# schematic_ad15.net
KiCad netlist of a schematic drawn in Altium Designer
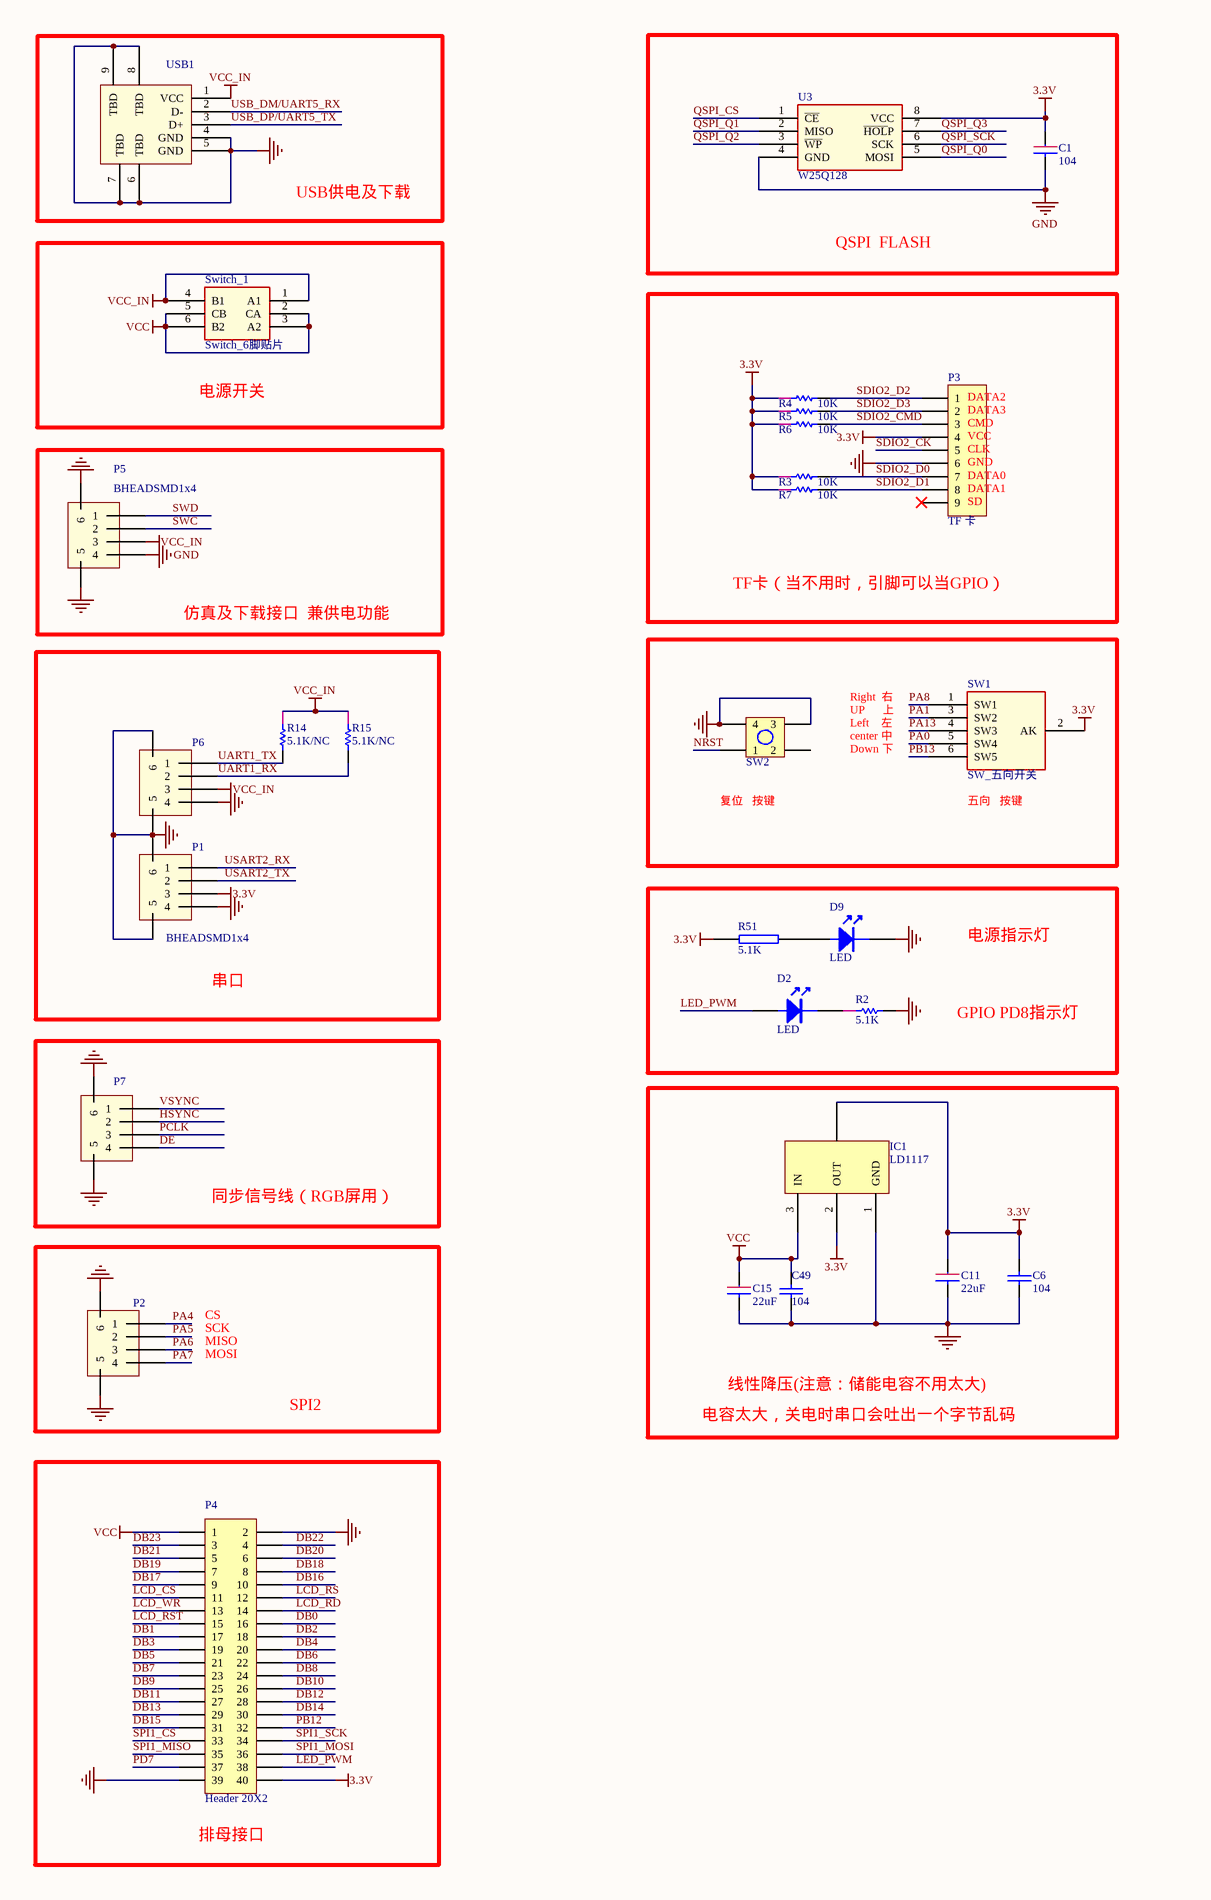
[diagram p0: schematic_ad15.SchDoc, left]
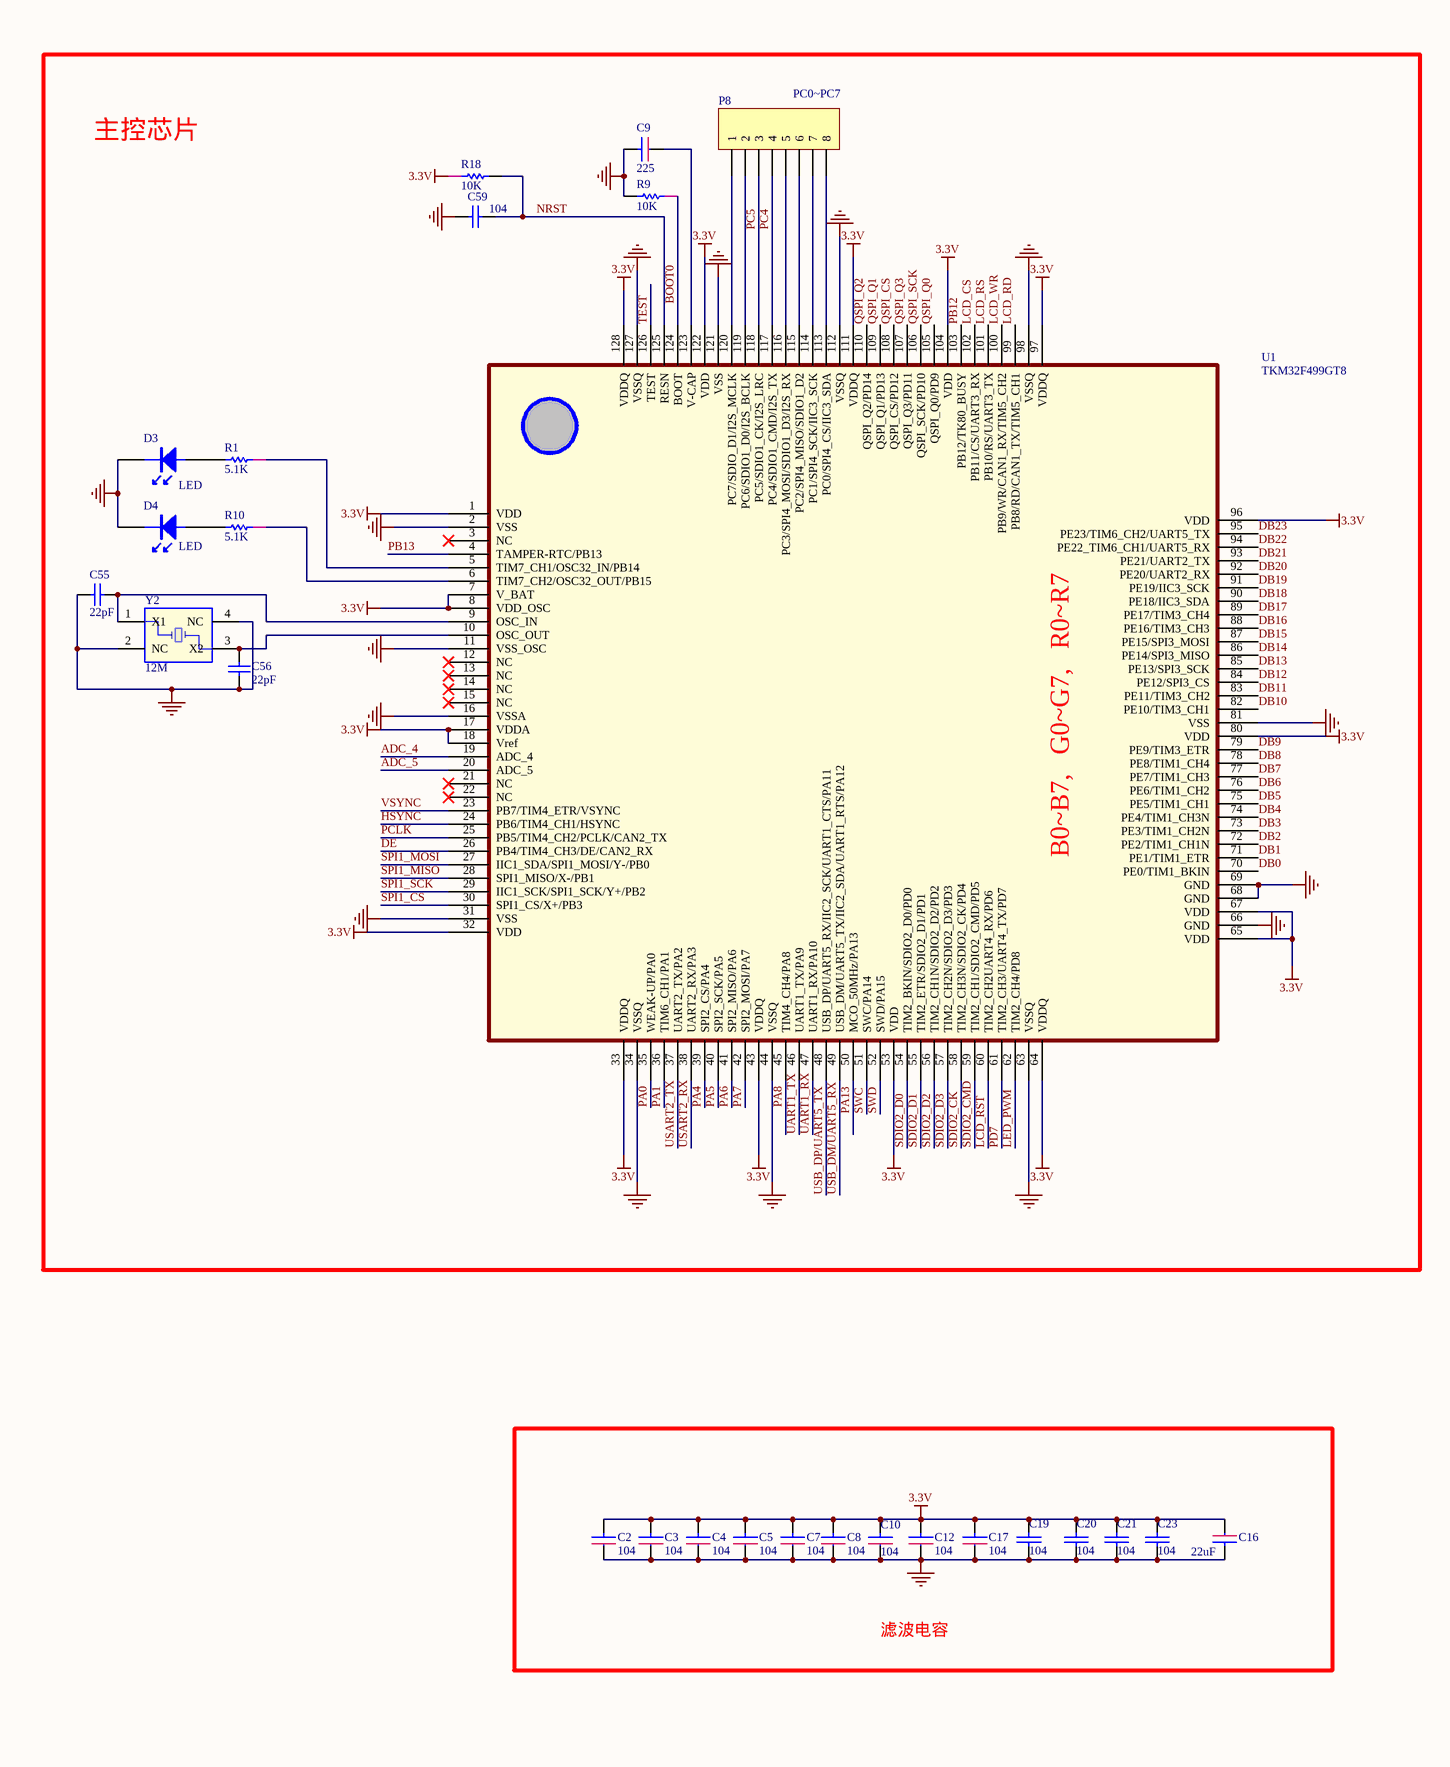
[diagram p1: schematic_ad15.SchDoc, right]

(export (version "E")
  (design (tool "Eeschema 10.0.6"))
  (components
    (comp (ref "C1") (value "104") (footprint "C0402-1") (libsource (lib "Tiky") (part "cap")))
    (comp (ref "C2") (value "104") (footprint "C0402-1") (libsource (lib "Tiky") (part "cap")))
    (comp (ref "C3") (value "104") (footprint "C0402-1") (libsource (lib "Tiky") (part "cap")))
    (comp (ref "C4") (value "104") (footprint "C0402-1") (libsource (lib "Tiky") (part "cap")))
    (comp (ref "C5") (value "104") (footprint "C0402-1") (libsource (lib "Tiky") (part "cap")))
    (comp (ref "C6")
      (value "104")
      (footprint "C0402-1")
      (description "Capacitor")
      (libsource (lib "Miscellaneous Devices") (part "CAP"))
    )
    (comp (ref "C7") (value "104") (footprint "C0402-1") (libsource (lib "Tiky") (part "cap")))
    (comp (ref "C8") (value "104") (footprint "C0402-1") (libsource (lib "Tiky") (part "cap")))
    (comp (ref "C9") (value "225") (footprint "C0603-2") (libsource (lib "Tiky") (part "cap")))
    (comp (ref "C10") (value "104") (footprint "C0402-1") (libsource (lib "Tiky") (part "cap")))
    (comp (ref "C11") (value "22uF") (footprint "Case B 3528") (libsource (lib "Tiky") (part "cap")))
    (comp (ref "C12") (value "104") (footprint "C0402-1") (libsource (lib "Tiky") (part "cap")))
    (comp (ref "C15") (value "22uF") (footprint "Case B 3528") (libsource (lib "Tiky") (part "cap")))
    (comp (ref "C16") (value "22uF") (footprint "C0805-3") (libsource (lib "Tiky") (part "cap")))
    (comp (ref "C17") (value "104") (footprint "C0402-1") (libsource (lib "Tiky") (part "cap")))
    (comp (ref "C19")
      (value "104")
      (footprint "C0402-1")
      (description "Capacitor")
      (libsource (lib "*") (part "CAP"))
    )
    (comp (ref "C20")
      (value "104")
      (footprint "C0402-1")
      (description "Capacitor")
      (libsource (lib "*") (part "CAP"))
    )
    (comp (ref "C21")
      (value "104")
      (footprint "C0402-1")
      (description "Capacitor")
      (libsource (lib "*") (part "CAP"))
    )
    (comp (ref "C23")
      (value "104")
      (footprint "C0402-1")
      (description "Capacitor")
      (libsource (lib "*") (part "CAP"))
    )
    (comp (ref "C49")
      (value "104")
      (footprint "C0402-1")
      (description "Capacitor")
      (libsource (lib "*") (part "CAP"))
    )
    (comp (ref "C55")
      (value "22pF")
      (footprint "C0402-2")
      (description "Capacitor")
      (fields (field (name "PUBLISHER") "Altium Limited"))
      (libsource (lib "Miscellaneous Devices") (part "Cap"))
    )
    (comp (ref "C56")
      (value "22pF")
      (footprint "C0402-2")
      (description "Capacitor")
      (fields (field (name "PUBLISHER") "Altium Limited"))
      (libsource (lib "Miscellaneous Devices") (part "Cap"))
    )
    (comp (ref "C59")
      (value "104")
      (footprint "C0402-1")
      (description "Capacitor")
      (fields (field (name "PUBLISHER") "Altium Limited"))
      (libsource (lib "") (part "CAP_1"))
    )
    (comp (ref "D2") (value "LED") (footprint "D0603") (libsource (lib "*") (part "LED")))
    (comp (ref "D3") (value "LED") (footprint "D0603") (libsource (lib "*") (part "LED")))
    (comp (ref "D4") (value "LED") (footprint "D0603") (libsource (lib "*") (part "LED")))
    (comp (ref "D9") (value "LED") (footprint "D0603") (libsource (lib "*") (part "LED")))
    (comp (ref "IC1") (value "LD1117") (footprint "SOT223") (libsource (lib "Tiky") (part "LD1117")))
    (comp (ref "P1")
      (value "BHEADSMD1x4")
      (footprint "BHEADSMD1x4")
      (libsource (lib "Tiky") (part "BHEADSMD1x4"))
    )
    (comp (ref "P2")
      (value "BHEADSMD1x4")
      (footprint "BHEADSMD1x4")
      (libsource (lib "Tiky") (part "BHEADSMD1x4"))
    )
    (comp (ref "P3")
      (value "TF 卡")
      (footprint "Micro_SD")
      (description "Header, 9-Pin")
      (fields (field (name "PUBLISHER") "Altium Limited"))
      (libsource (lib "Miscellaneous Connectors") (part "Header 9"))
    )
    (comp (ref "P4")
      (value "Header 20X2")
      (footprint "P_Head_2x20")
      (description "Header, 20-Pin, Dual row")
      (fields (field (name "PUBLISHER") "Altium Limited"))
      (libsource (lib "Miscellaneous Connectors") (part "Header 20X2"))
    )
    (comp (ref "P5")
      (value "BHEADSMD1x4")
      (footprint "BHEADSMD1x4")
      (libsource (lib "Tiky") (part "BHEADSMD1x4"))
    )
    (comp (ref "P6")
      (value "BHEADSMD1x4")
      (footprint "BHEADSMD1x4")
      (libsource (lib "Tiky") (part "BHEADSMD1x4"))
    )
    (comp (ref "P7")
      (value "BHEADSMD1x4")
      (footprint "BHEADSMD1x4")
      (libsource (lib "Tiky") (part "BHEADSMD1x4"))
    )
    (comp (ref "P8")
      (value "PC0~PC7")
      (footprint "HDR1X8")
      (description "Header, 8-Pin")
      (fields (field (name "PUBLISHER") "Altium Limited"))
      (libsource (lib "Miscellaneous Connectors") (part "Header 8"))
    )
    (comp (ref "R1") (value "5.1K") (footprint "R0402") (libsource (lib "Tiky") (part "Resistor")))
    (comp (ref "R2") (value "5.1K") (footprint "R0402") (libsource (lib "Tiky") (part "Resistor")))
    (comp (ref "R3") (value "10K") (footprint "R0402") (libsource (lib "Tiky") (part "Resistor")))
    (comp (ref "R4") (value "10K") (footprint "R0402") (libsource (lib "Tiky") (part "Resistor")))
    (comp (ref "R5") (value "10K") (footprint "R0402") (libsource (lib "Tiky") (part "Resistor")))
    (comp (ref "R6") (value "10K") (footprint "R0402") (libsource (lib "Tiky") (part "Resistor")))
    (comp (ref "R7") (value "10K") (footprint "R0402") (libsource (lib "Tiky") (part "Resistor")))
    (comp (ref "R9") (value "10K") (footprint "R0402") (libsource (lib "Tiky") (part "Resistor")))
    (comp (ref "R10") (value "5.1K") (footprint "R0402") (libsource (lib "Tiky") (part "Resistor")))
    (comp (ref "R14") (value "5.1K/NC") (footprint "R0402") (libsource (lib "Tiky") (part "Resistor")))
    (comp (ref "R15") (value "5.1K/NC") (footprint "R0402") (libsource (lib "Tiky") (part "Resistor")))
    (comp (ref "R18") (value "10K") (footprint "R0402") (libsource (lib "Tiky") (part "Resistor")))
    (comp (ref "R51") (value "5.1K") (footprint "R0402") (libsource (lib "*") (part "RES2")))
    (comp (ref "SW1") (value "SW_五向开关") (footprint "五向开关") (libsource (lib "Tiky") (part "SW_五向开关")))
    (comp (ref "SW2") (value "SW") (footprint "SW") (libsource (lib "Tiky") (part "SW")))
    (comp (ref "Switch_1")
      (value "Switch_6脚贴片")
      (footprint "Switch_6脚贴片")
      (libsource (lib "Tiky") (part "Switch_6脚贴片"))
    )
    (comp (ref "U1")
      (value "TKM32F499GT8")
      (footprint "LQFP128")
      (libsource (lib "Tiky") (part "TKM32F499GT8"))
    )
    (comp (ref "U3") (value "W25Q128") (footprint "SOP8-215-50") (libsource (lib "Tiky") (part "W25Q16")))
    (comp (ref "USB1")
      (value "Micro USB")
      (footprint "MicroUSB_带定位柱")
      (libsource (lib "Tiky") (part "Mini USB"))
    )
    (comp (ref "Y2") (value "12M") (footprint "X3225") (libsource (lib "Tiky") (part "晶振_无源_4PIN_SMD")))
  )
  (nets
    (net (code "1") (name "/ADC_4") (class "Default")
      (node (ref "U1") (pin "19") (pinfunction "ADC_4_19") (pintype "passive"))
    )
    (net (code "2") (name "/ADC_5") (class "Default")
      (node (ref "U1") (pin "20") (pinfunction "ADC_5_20") (pintype "passive"))
    )
    (net (code "3") (name "/BOOT0") (class "Default")
      (node (ref "R9") (pin "1") (pinfunction "1_1") (pintype "passive"))
      (node (ref "U1") (pin "124") (pinfunction "BOOT_124") (pintype "passive"))
    )
    (net (code "4") (name "/DB0") (class "Default")
      (node (ref "P4") (pin "16") (pinfunction "16_16") (pintype "passive"))
      (node (ref "U1") (pin "70") (pinfunction "PE0/TIM1_BKIN_70") (pintype "passive"))
    )
    (net (code "5") (name "/DB1") (class "Default")
      (node (ref "P4") (pin "17") (pinfunction "17_17") (pintype "passive"))
      (node (ref "U1") (pin "71") (pinfunction "PE1/TIM1_ETR_71") (pintype "passive"))
    )
    (net (code "6") (name "/DB2") (class "Default")
      (node (ref "P4") (pin "18") (pinfunction "18_18") (pintype "passive"))
      (node (ref "U1") (pin "72") (pinfunction "PE2/TIM1_CH1N_72") (pintype "passive"))
    )
    (net (code "7") (name "/DB3") (class "Default")
      (node (ref "P4") (pin "19") (pinfunction "19_19") (pintype "passive"))
      (node (ref "U1") (pin "73") (pinfunction "PE3/TIM1_CH2N_73") (pintype "passive"))
    )
    (net (code "8") (name "/DB4") (class "Default")
      (node (ref "P4") (pin "20") (pinfunction "20_20") (pintype "passive"))
      (node (ref "U1") (pin "74") (pinfunction "PE4/TIM1_CH3N_74") (pintype "passive"))
    )
    (net (code "9") (name "/DB5") (class "Default")
      (node (ref "P4") (pin "21") (pinfunction "21_21") (pintype "passive"))
      (node (ref "U1") (pin "75") (pinfunction "PE5/TIM1_CH1_75") (pintype "passive"))
    )
    (net (code "10") (name "/DB6") (class "Default")
      (node (ref "P4") (pin "22") (pinfunction "22_22") (pintype "passive"))
      (node (ref "U1") (pin "76") (pinfunction "PE6/TIM1_CH2_76") (pintype "passive"))
    )
    (net (code "11") (name "/DB7") (class "Default")
      (node (ref "P4") (pin "23") (pinfunction "23_23") (pintype "passive"))
      (node (ref "U1") (pin "77") (pinfunction "PE7/TIM1_CH3_77") (pintype "passive"))
    )
    (net (code "12") (name "/DB8") (class "Default")
      (node (ref "P4") (pin "24") (pinfunction "24_24") (pintype "passive"))
      (node (ref "U1") (pin "78") (pinfunction "PE8/TIM1_CH4_78") (pintype "passive"))
    )
    (net (code "13") (name "/DB9") (class "Default")
      (node (ref "P4") (pin "25") (pinfunction "25_25") (pintype "passive"))
      (node (ref "U1") (pin "79") (pinfunction "PE9/TIM3_ETR_79") (pintype "passive"))
    )
    (net (code "14") (name "/DB10") (class "Default")
      (node (ref "P4") (pin "26") (pinfunction "26_26") (pintype "passive"))
      (node (ref "U1") (pin "82") (pinfunction "PE10/TIM3_CH1_82") (pintype "passive"))
    )
    (net (code "15") (name "/DB11") (class "Default")
      (node (ref "P4") (pin "27") (pinfunction "27_27") (pintype "passive"))
      (node (ref "U1") (pin "83") (pinfunction "PE11/TIM3_CH2_83") (pintype "passive"))
    )
    (net (code "16") (name "/DB12") (class "Default")
      (node (ref "P4") (pin "28") (pinfunction "28_28") (pintype "passive"))
      (node (ref "U1") (pin "84") (pinfunction "PE12/SPI3_CS_84") (pintype "passive"))
    )
    (net (code "17") (name "/DB13") (class "Default")
      (node (ref "P4") (pin "29") (pinfunction "29_29") (pintype "passive"))
      (node (ref "U1") (pin "85") (pinfunction "PE13/SPI3_SCK_85") (pintype "passive"))
    )
    (net (code "18") (name "/DB14") (class "Default")
      (node (ref "P4") (pin "30") (pinfunction "30_30") (pintype "passive"))
      (node (ref "U1") (pin "86") (pinfunction "PE14/SPI3_MISO_86") (pintype "passive"))
    )
    (net (code "19") (name "/DB15") (class "Default")
      (node (ref "P4") (pin "31") (pinfunction "31_31") (pintype "passive"))
      (node (ref "U1") (pin "87") (pinfunction "PE15/SPI3_MOSI_87") (pintype "passive"))
    )
    (net (code "20") (name "/DB16") (class "Default")
      (node (ref "P4") (pin "10") (pinfunction "10_10") (pintype "passive"))
      (node (ref "U1") (pin "88") (pinfunction "PE16/TIM3_CH3_88") (pintype "passive"))
    )
    (net (code "21") (name "/DB17") (class "Default")
      (node (ref "P4") (pin "9") (pinfunction "9_9") (pintype "passive"))
      (node (ref "U1") (pin "89") (pinfunction "PE17/TIM3_CH4_89") (pintype "passive"))
    )
    (net (code "22") (name "/DB18") (class "Default")
      (node (ref "P4") (pin "8") (pinfunction "8_8") (pintype "passive"))
      (node (ref "U1") (pin "90") (pinfunction "PE18/IIC3_SDA_90") (pintype "passive"))
    )
    (net (code "23") (name "/DB19") (class "Default")
      (node (ref "P4") (pin "7") (pinfunction "7_7") (pintype "passive"))
      (node (ref "U1") (pin "91") (pinfunction "PE19/IIC3_SCK_91") (pintype "passive"))
    )
    (net (code "24") (name "/DB20") (class "Default")
      (node (ref "P4") (pin "6") (pinfunction "6_6") (pintype "passive"))
      (node (ref "U1") (pin "92") (pinfunction "PE20/UART2_RX_92") (pintype "passive"))
    )
    (net (code "25") (name "/DB21") (class "Default")
      (node (ref "P4") (pin "5") (pinfunction "5_5") (pintype "passive"))
      (node (ref "U1") (pin "93") (pinfunction "PE21/UART2_TX_93") (pintype "passive"))
    )
    (net (code "26") (name "/DB22") (class "Default")
      (node (ref "P4") (pin "4") (pinfunction "4_4") (pintype "passive"))
      (node (ref "U1") (pin "94") (pinfunction "PE22_TIM6_CH1/UART5_RX_94") (pintype "passive"))
    )
    (net (code "27") (name "/DB23") (class "Default")
      (node (ref "P4") (pin "3") (pinfunction "3_3") (pintype "passive"))
      (node (ref "U1") (pin "95") (pinfunction "PE23/TIM6_CH2/UART5_TX_95") (pintype "passive"))
    )
    (net (code "28") (name "/DE") (class "Default")
      (node (ref "P7") (pin "4") (pinfunction "4_4") (pintype "passive"))
      (node (ref "U1") (pin "26") (pinfunction "PB4/TIM4_CH3/DE/CAN2_RX_26") (pintype "passive"))
    )
    (net (code "29") (name "/HSYNC") (class "Default")
      (node (ref "P7") (pin "2") (pinfunction "2_2") (pintype "passive"))
      (node (ref "U1") (pin "24") (pinfunction "PB6/TIM4_CH1/HSYNC_24") (pintype "passive"))
    )
    (net (code "30") (name "/LCD_CS") (class "Default")
      (node (ref "P4") (pin "11") (pinfunction "11_11") (pintype "passive"))
      (node (ref "U1") (pin "102") (pinfunction "PB11/CS/UART3_RX_102") (pintype "passive"))
    )
    (net (code "31") (name "/LCD_RD") (class "Default")
      (node (ref "P4") (pin "14") (pinfunction "14_14") (pintype "passive"))
      (node (ref "U1") (pin "99") (pinfunction "PB8/RD/CAN1_TX/TIM5_CH1_99") (pintype "passive"))
    )
    (net (code "32") (name "/LCD_RS") (class "Default")
      (node (ref "P4") (pin "12") (pinfunction "12_12") (pintype "passive"))
      (node (ref "U1") (pin "101") (pinfunction "PB10/RS/UART3_TX_101") (pintype "passive"))
    )
    (net (code "33") (name "/LCD_RST") (class "Default")
      (node (ref "P4") (pin "15") (pinfunction "15_15") (pintype "passive"))
      (node (ref "U1") (pin "60") (pinfunction "TIM2_CH2UART4_RX/PD6_60") (pintype "passive"))
    )
    (net (code "34") (name "/LCD_WR") (class "Default")
      (node (ref "P4") (pin "13") (pinfunction "13_13") (pintype "passive"))
      (node (ref "U1") (pin "100") (pinfunction "PB9/WR/CAN1_RX/TIM5_CH2_100") (pintype "passive"))
    )
    (net (code "35") (name "/LED_PWM") (class "Default")
      (node (ref "D2") (pin "1") (pinfunction "1_1") (pintype "passive"))
      (node (ref "P4") (pin "38") (pinfunction "38_38") (pintype "passive"))
      (node (ref "U1") (pin "62") (pinfunction "TIM2_CH4/PD8_62") (pintype "passive"))
    )
    (net (code "36") (name "/NRST") (class "Default")
      (node (ref "C59") (pin "2") (pinfunction "2_2") (pintype "passive"))
      (node (ref "R18") (pin "2") (pinfunction "2_2") (pintype "passive"))
      (node (ref "SW2") (pin "1") (pinfunction "1_1") (pintype "passive"))
      (node (ref "U1") (pin "125") (pinfunction "RESN_125") (pintype "passive"))
    )
    (net (code "37") (name "/PA0") (class "Default")
      (node (ref "SW1") (pin "5") (pinfunction "SW4_5") (pintype "passive"))
      (node (ref "U1") (pin "35") (pinfunction "WEAK-UP/PA0_35") (pintype "passive"))
    )
    (net (code "38") (name "/PA1") (class "Default")
      (node (ref "SW1") (pin "3") (pinfunction "SW2_3") (pintype "passive"))
      (node (ref "U1") (pin "36") (pinfunction "TIM6_CH1/PA1_36") (pintype "passive"))
    )
    (net (code "39") (name "/PA4") (class "Default")
      (node (ref "P2") (pin "1") (pinfunction "1_1") (pintype "passive"))
      (node (ref "U1") (pin "39") (pinfunction "SPI2_CS/PA4_39") (pintype "passive"))
    )
    (net (code "40") (name "/PA5") (class "Default")
      (node (ref "P2") (pin "2") (pinfunction "2_2") (pintype "passive"))
      (node (ref "U1") (pin "40") (pinfunction "SPI2_SCK/PA5_40") (pintype "passive"))
    )
    (net (code "41") (name "/PA6") (class "Default")
      (node (ref "P2") (pin "3") (pinfunction "3_3") (pintype "passive"))
      (node (ref "U1") (pin "41") (pinfunction "SPI2_MISO/PA6_41") (pintype "passive"))
    )
    (net (code "42") (name "/PA7") (class "Default")
      (node (ref "P2") (pin "4") (pinfunction "4_4") (pintype "passive"))
      (node (ref "U1") (pin "42") (pinfunction "SPI2_MOSI/PA7_42") (pintype "passive"))
    )
    (net (code "43") (name "/PA8") (class "Default")
      (node (ref "SW1") (pin "1") (pinfunction "SW1_1") (pintype "passive"))
      (node (ref "U1") (pin "45") (pinfunction "TIM4_CH4/PA8_45") (pintype "passive"))
    )
    (net (code "44") (name "/PA13") (class "Default")
      (node (ref "SW1") (pin "4") (pinfunction "SW3_4") (pintype "passive"))
      (node (ref "U1") (pin "50") (pinfunction "MCO_50MHz/PA13_50") (pintype "passive"))
    )
    (net (code "45") (name "/PB12") (class "Default")
      (node (ref "P4") (pin "32") (pinfunction "32_32") (pintype "passive"))
      (node (ref "U1") (pin "103") (pinfunction "PB12/TK80_BUSY_103") (pintype "passive"))
    )
    (net (code "46") (name "/PB13") (class "Default")
      (node (ref "SW1") (pin "6") (pinfunction "SW5_6") (pintype "passive"))
      (node (ref "U1") (pin "4") (pinfunction "TAMPER-RTC/PB13_4") (pintype "passive"))
    )
    (net (code "47") (name "/PC4") (class "Default")
      (node (ref "P8") (pin "4") (pinfunction "4_4") (pintype "passive"))
      (node (ref "U1") (pin "117") (pinfunction "PC4/SDIO1_CMD/I2S_TX_117") (pintype "passive"))
    )
    (net (code "48") (name "/PC5") (class "Default")
      (node (ref "P8") (pin "3") (pinfunction "3_3") (pintype "passive"))
      (node (ref "U1") (pin "118") (pinfunction "PC5/SDIO1_CK/I2S_LRC_118") (pintype "passive"))
    )
    (net (code "49") (name "/PCLK") (class "Default")
      (node (ref "P7") (pin "3") (pinfunction "3_3") (pintype "passive"))
      (node (ref "U1") (pin "25") (pinfunction "PB5/TIM4_CH2/PCLK/CAN2_TX_25") (pintype "passive"))
    )
    (net (code "50") (name "/PD7") (class "Default")
      (node (ref "P4") (pin "37") (pinfunction "37_37") (pintype "passive"))
      (node (ref "U1") (pin "61") (pinfunction "TIM2_CH3/UART4_TX/PD7_61") (pintype "passive"))
    )
    (net (code "51") (name "/QSPI_CS") (class "Default")
      (node (ref "U1") (pin "108") (pinfunction "QSPI_CS/PD12_108") (pintype "passive"))
      (node (ref "U3") (pin "1") (pinfunction "~{CE}_1") (pintype "passive"))
    )
    (net (code "52") (name "/QSPI_Q0") (class "Default")
      (node (ref "U1") (pin "105") (pinfunction "QSPI_Q0/PD9_105") (pintype "passive"))
      (node (ref "U3") (pin "5") (pinfunction "MOSI_5") (pintype "passive"))
    )
    (net (code "53") (name "/QSPI_Q1") (class "Default")
      (node (ref "U1") (pin "109") (pinfunction "QSPI_Q1/PD13_109") (pintype "passive"))
      (node (ref "U3") (pin "2") (pinfunction "MISO_2") (pintype "passive"))
    )
    (net (code "54") (name "/QSPI_Q2") (class "Default")
      (node (ref "U1") (pin "110") (pinfunction "QSPI_Q2/PD14_110") (pintype "passive"))
      (node (ref "U3") (pin "3") (pinfunction "~{WP}_3") (pintype "passive"))
    )
    (net (code "55") (name "/QSPI_Q3") (class "Default")
      (node (ref "U1") (pin "107") (pinfunction "QSPI_Q3/PD11_107") (pintype "passive"))
      (node (ref "U3") (pin "7") (pinfunction "~{HOL}P_7") (pintype "passive"))
    )
    (net (code "56") (name "/QSPI_SCK") (class "Default")
      (node (ref "U1") (pin "106") (pinfunction "QSPI_SCK/PD10_106") (pintype "passive"))
      (node (ref "U3") (pin "6") (pinfunction "SCK_6") (pintype "passive"))
    )
    (net (code "57") (name "/SDIO2_CK") (class "Default")
      (node (ref "P3") (pin "5") (pinfunction "5_5") (pintype "passive"))
      (node (ref "U1") (pin "58") (pinfunction "TIM2_CH3N/SDIO2_CK/PD4_58") (pintype "passive"))
    )
    (net (code "58") (name "/SDIO2_CMD") (class "Default")
      (node (ref "P3") (pin "3") (pinfunction "3_3") (pintype "passive"))
      (node (ref "R6") (pin "2") (pinfunction "2_2") (pintype "passive"))
      (node (ref "U1") (pin "59") (pinfunction "TIM2_CH1/SDIO2_CMD/PD5_59") (pintype "passive"))
    )
    (net (code "59") (name "/SDIO2_D0") (class "Default")
      (node (ref "P3") (pin "7") (pinfunction "7_7") (pintype "passive"))
      (node (ref "R3") (pin "2") (pinfunction "2_2") (pintype "passive"))
      (node (ref "U1") (pin "54") (pinfunction "TIM2_BKIN/SDIO2_D0/PD0_54") (pintype "passive"))
    )
    (net (code "60") (name "/SDIO2_D1") (class "Default")
      (node (ref "P3") (pin "8") (pinfunction "8_8") (pintype "passive"))
      (node (ref "R7") (pin "2") (pinfunction "2_2") (pintype "passive"))
      (node (ref "U1") (pin "55") (pinfunction "TIM2_ETR/SDIO2_D1/PD1_55") (pintype "passive"))
    )
    (net (code "61") (name "/SDIO2_D2") (class "Default")
      (node (ref "P3") (pin "1") (pinfunction "1_1") (pintype "passive"))
      (node (ref "R4") (pin "2") (pinfunction "2_2") (pintype "passive"))
      (node (ref "U1") (pin "56") (pinfunction "TIM2_CH1N/SDIO2_D2/PD2_56") (pintype "passive"))
    )
    (net (code "62") (name "/SDIO2_D3") (class "Default")
      (node (ref "P3") (pin "2") (pinfunction "2_2") (pintype "passive"))
      (node (ref "R5") (pin "2") (pinfunction "2_2") (pintype "passive"))
      (node (ref "U1") (pin "57") (pinfunction "TIM2_CH2N/SDIO2_D3/PD3_57") (pintype "passive"))
    )
    (net (code "63") (name "/SPI1_CS") (class "Default")
      (node (ref "P4") (pin "33") (pinfunction "33_33") (pintype "passive"))
      (node (ref "U1") (pin "30") (pinfunction "SPI1_CS/X+/PB3_30") (pintype "passive"))
    )
    (net (code "64") (name "/SPI1_MISO") (class "Default")
      (node (ref "P4") (pin "35") (pinfunction "35_35") (pintype "passive"))
      (node (ref "U1") (pin "28") (pinfunction "SPI1_MISO/X-/PB1_28") (pintype "passive"))
    )
    (net (code "65") (name "/SPI1_MOSI") (class "Default")
      (node (ref "P4") (pin "36") (pinfunction "36_36") (pintype "passive"))
      (node (ref "U1") (pin "27") (pinfunction "IIC1_SDA/SPI1_MOSI/Y-/PB0_27") (pintype "passive"))
    )
    (net (code "66") (name "/SPI1_SCK") (class "Default")
      (node (ref "P4") (pin "34") (pinfunction "34_34") (pintype "passive"))
      (node (ref "U1") (pin "29") (pinfunction "IIC1_SCK/SPI1_SCK/Y+/PB2_29") (pintype "passive"))
    )
    (net (code "67") (name "/SWC") (class "Default")
      (node (ref "P5") (pin "2") (pinfunction "2_2") (pintype "passive"))
      (node (ref "U1") (pin "51") (pinfunction "SWC/PA14_51") (pintype "passive"))
    )
    (net (code "68") (name "/SWD") (class "Default")
      (node (ref "P5") (pin "1") (pinfunction "1_1") (pintype "passive"))
      (node (ref "U1") (pin "52") (pinfunction "SWD/PA15_52") (pintype "passive"))
    )
    (net (code "69") (name "/TEST") (class "Default")
      (node (ref "U1") (pin "126") (pinfunction "TEST_126") (pintype "passive"))
    )
    (net (code "70") (name "/UART1_RX") (class "Default")
      (node (ref "P6") (pin "2") (pinfunction "2_2") (pintype "passive"))
      (node (ref "R15") (pin "2") (pinfunction "2_2") (pintype "passive"))
      (node (ref "U1") (pin "47") (pinfunction "UART1_RX/PA10_47") (pintype "passive"))
    )
    (net (code "71") (name "/UART1_TX") (class "Default")
      (node (ref "P6") (pin "1") (pinfunction "1_1") (pintype "passive"))
      (node (ref "R14") (pin "2") (pinfunction "2_2") (pintype "passive"))
      (node (ref "U1") (pin "46") (pinfunction "UART1_TX/PA9_46") (pintype "passive"))
    )
    (net (code "72") (name "/USART2_RX") (class "Default")
      (node (ref "P1") (pin "1") (pinfunction "1_1") (pintype "passive"))
      (node (ref "U1") (pin "38") (pinfunction "UART2_RX/PA3_38") (pintype "passive"))
    )
    (net (code "73") (name "/USART2_TX") (class "Default")
      (node (ref "P1") (pin "2") (pinfunction "2_2") (pintype "passive"))
      (node (ref "U1") (pin "37") (pinfunction "UART2_TX/PA2_37") (pintype "passive"))
    )
    (net (code "74") (name "/USB_DM{slash}UART5_RX") (class "Default")
      (node (ref "U1") (pin "49") (pinfunction "USB_DM/UART5_TX/IIC2_SDA/UART1_RTS/PA12_49") (pintype "passive"))
      (node (ref "USB1") (pin "2") (pinfunction "D-_2") (pintype "passive"))
    )
    (net (code "75") (name "/USB_DP{slash}UART5_TX") (class "Default")
      (node (ref "U1") (pin "48") (pinfunction "USB_DP/UART5_RX/IIC2_SCK/UART1_CTS/PA11_48") (pintype "passive"))
      (node (ref "USB1") (pin "3") (pinfunction "D+_3") (pintype "passive"))
    )
    (net (code "76") (name "/VSYNC") (class "Default")
      (node (ref "P7") (pin "1") (pinfunction "1_1") (pintype "passive"))
      (node (ref "U1") (pin "23") (pinfunction "PB7/TIM4_ETR/VSYNC_23") (pintype "passive"))
    )
    (net (code "77") (name "3.3V") (class "Default")
      (node (ref "C1") (pin "1") (pinfunction "1_1") (pintype "passive"))
      (node (ref "C10") (pin "2") (pinfunction "2_2") (pintype "passive"))
      (node (ref "C11") (pin "1") (pinfunction "1_1") (pintype "passive"))
      (node (ref "C12") (pin "2") (pinfunction "2_2") (pintype "passive"))
      (node (ref "C16") (pin "1") (pinfunction "1_1") (pintype "passive"))
      (node (ref "C17") (pin "2") (pinfunction "2_2") (pintype "passive"))
      (node (ref "C19") (pin "2") (pinfunction "2_2") (pintype "passive"))
      (node (ref "C2") (pin "2") (pinfunction "2_2") (pintype "passive"))
      (node (ref "C20") (pin "2") (pinfunction "2_2") (pintype "passive"))
      (node (ref "C21") (pin "2") (pinfunction "2_2") (pintype "passive"))
      (node (ref "C23") (pin "2") (pinfunction "2_2") (pintype "passive"))
      (node (ref "C3") (pin "2") (pinfunction "2_2") (pintype "passive"))
      (node (ref "C4") (pin "2") (pinfunction "2_2") (pintype "passive"))
      (node (ref "C5") (pin "2") (pinfunction "2_2") (pintype "passive"))
      (node (ref "C6") (pin "1") (pinfunction "1_1") (pintype "passive"))
      (node (ref "C7") (pin "2") (pinfunction "2_2") (pintype "passive"))
      (node (ref "C8") (pin "2") (pinfunction "2_2") (pintype "passive"))
      (node (ref "IC1") (pin "2") (pinfunction "OUT_2") (pintype "passive"))
      (node (ref "P1") (pin "3") (pinfunction "3_3") (pintype "passive"))
      (node (ref "P3") (pin "4") (pinfunction "4_4") (pintype "passive"))
      (node (ref "P4") (pin "40") (pinfunction "40_40") (pintype "passive"))
      (node (ref "R18") (pin "1") (pinfunction "1_1") (pintype "passive"))
      (node (ref "R3") (pin "1") (pinfunction "1_1") (pintype "passive"))
      (node (ref "R4") (pin "1") (pinfunction "1_1") (pintype "passive"))
      (node (ref "R5") (pin "1") (pinfunction "1_1") (pintype "passive"))
      (node (ref "R51") (pin "1") (pinfunction "1_1") (pintype "passive"))
      (node (ref "R6") (pin "1") (pinfunction "1_1") (pintype "passive"))
      (node (ref "R7") (pin "1") (pinfunction "1_1") (pintype "passive"))
      (node (ref "SW1") (pin "2") (pinfunction "AK_2") (pintype "passive"))
      (node (ref "U1") (pin "1") (pinfunction "VDD_1") (pintype "passive"))
      (node (ref "U1") (pin "104") (pinfunction "VDD_104") (pintype "passive"))
      (node (ref "U1") (pin "111") (pinfunction "VDDQ_111") (pintype "passive"))
      (node (ref "U1") (pin "122") (pinfunction "VDD_122") (pintype "passive"))
      (node (ref "U1") (pin "128") (pinfunction "VDDQ_128") (pintype "passive"))
      (node (ref "U1") (pin "17") (pinfunction "VDDA_17") (pintype "passive"))
      (node (ref "U1") (pin "18") (pinfunction "Vref_18") (pintype "passive"))
      (node (ref "U1") (pin "32") (pinfunction "VDD_32") (pintype "passive"))
      (node (ref "U1") (pin "33") (pinfunction "VDDQ_33") (pintype "passive"))
      (node (ref "U1") (pin "43") (pinfunction "VDDQ_43") (pintype "passive"))
      (node (ref "U1") (pin "53") (pinfunction "VDD_53") (pintype "passive"))
      (node (ref "U1") (pin "64") (pinfunction "VDDQ_64") (pintype "passive"))
      (node (ref "U1") (pin "65") (pinfunction "VDD_65") (pintype "passive"))
      (node (ref "U1") (pin "67") (pinfunction "VDD_67") (pintype "passive"))
      (node (ref "U1") (pin "7") (pinfunction "V_BAT_7") (pintype "passive"))
      (node (ref "U1") (pin "8") (pinfunction "VDD_OSC_8") (pintype "passive"))
      (node (ref "U1") (pin "80") (pinfunction "VDD_80") (pintype "passive"))
      (node (ref "U1") (pin "96") (pinfunction "VDD_96") (pintype "passive"))
      (node (ref "U1") (pin "97") (pinfunction "VDDQ_97") (pintype "passive"))
      (node (ref "U3") (pin "8") (pinfunction "VCC_8") (pintype "passive"))
    )
    (net (code "78") (name "GND") (class "Default")
      (node (ref "C1") (pin "2") (pinfunction "2_2") (pintype "passive"))
      (node (ref "C10") (pin "1") (pinfunction "1_1") (pintype "passive"))
      (node (ref "C11") (pin "2") (pinfunction "2_2") (pintype "passive"))
      (node (ref "C12") (pin "1") (pinfunction "1_1") (pintype "passive"))
      (node (ref "C15") (pin "2") (pinfunction "2_2") (pintype "passive"))
      (node (ref "C16") (pin "2") (pinfunction "2_2") (pintype "passive"))
      (node (ref "C17") (pin "1") (pinfunction "1_1") (pintype "passive"))
      (node (ref "C19") (pin "1") (pinfunction "1_1") (pintype "passive"))
      (node (ref "C2") (pin "1") (pinfunction "1_1") (pintype "passive"))
      (node (ref "C20") (pin "1") (pinfunction "1_1") (pintype "passive"))
      (node (ref "C21") (pin "1") (pinfunction "1_1") (pintype "passive"))
      (node (ref "C23") (pin "1") (pinfunction "1_1") (pintype "passive"))
      (node (ref "C3") (pin "1") (pinfunction "1_1") (pintype "passive"))
      (node (ref "C4") (pin "1") (pinfunction "1_1") (pintype "passive"))
      (node (ref "C49") (pin "1") (pinfunction "1_1") (pintype "passive"))
      (node (ref "C5") (pin "1") (pinfunction "1_1") (pintype "passive"))
      (node (ref "C55") (pin "1") (pinfunction "1_1") (pintype "passive"))
      (node (ref "C56") (pin "1") (pinfunction "1_1") (pintype "passive"))
      (node (ref "C59") (pin "1") (pinfunction "1_1") (pintype "passive"))
      (node (ref "C6") (pin "2") (pinfunction "2_2") (pintype "passive"))
      (node (ref "C7") (pin "1") (pinfunction "1_1") (pintype "passive"))
      (node (ref "C8") (pin "1") (pinfunction "1_1") (pintype "passive"))
      (node (ref "C9") (pin "2") (pinfunction "2_2") (pintype "passive"))
      (node (ref "D3") (pin "2") (pinfunction "2_2") (pintype "passive"))
      (node (ref "D4") (pin "2") (pinfunction "2_2") (pintype "passive"))
      (node (ref "D9") (pin "2") (pinfunction "2_2") (pintype "passive"))
      (node (ref "IC1") (pin "1") (pinfunction "GND_1") (pintype "passive"))
      (node (ref "P1") (pin "4") (pinfunction "4_4") (pintype "passive"))
      (node (ref "P1") (pin "5") (pinfunction "5_5") (pintype "passive"))
      (node (ref "P1") (pin "6") (pinfunction "6_6") (pintype "passive"))
      (node (ref "P2") (pin "5") (pinfunction "5_5") (pintype "passive"))
      (node (ref "P2") (pin "6") (pinfunction "6_6") (pintype "passive"))
      (node (ref "P3") (pin "6") (pinfunction "6_6") (pintype "passive"))
      (node (ref "P4") (pin "2") (pinfunction "2_2") (pintype "passive"))
      (node (ref "P4") (pin "39") (pinfunction "39_39") (pintype "passive"))
      (node (ref "P5") (pin "4") (pinfunction "4_4") (pintype "passive"))
      (node (ref "P5") (pin "5") (pinfunction "5_5") (pintype "passive"))
      (node (ref "P5") (pin "6") (pinfunction "6_6") (pintype "passive"))
      (node (ref "P6") (pin "4") (pinfunction "4_4") (pintype "passive"))
      (node (ref "P6") (pin "5") (pinfunction "5_5") (pintype "passive"))
      (node (ref "P6") (pin "6") (pinfunction "6_6") (pintype "passive"))
      (node (ref "P7") (pin "5") (pinfunction "5_5") (pintype "passive"))
      (node (ref "P7") (pin "6") (pinfunction "6_6") (pintype "passive"))
      (node (ref "R2") (pin "2") (pinfunction "2_2") (pintype "passive"))
      (node (ref "R9") (pin "2") (pinfunction "2_2") (pintype "passive"))
      (node (ref "SW2") (pin "3") (pinfunction "3_3") (pintype "passive"))
      (node (ref "SW2") (pin "4") (pinfunction "4_4") (pintype "passive"))
      (node (ref "U1") (pin "11") (pinfunction "VSS_OSC_11") (pintype "passive"))
      (node (ref "U1") (pin "112") (pinfunction "VSSQ_112") (pintype "passive"))
      (node (ref "U1") (pin "121") (pinfunction "VSS_121") (pintype "passive"))
      (node (ref "U1") (pin "127") (pinfunction "VSSQ_127") (pintype "passive"))
      (node (ref "U1") (pin "16") (pinfunction "VSSA_16") (pintype "passive"))
      (node (ref "U1") (pin "2") (pinfunction "VSS_2") (pintype "passive"))
      (node (ref "U1") (pin "31") (pinfunction "VSS_31") (pintype "passive"))
      (node (ref "U1") (pin "34") (pinfunction "VSSQ_34") (pintype "passive"))
      (node (ref "U1") (pin "44") (pinfunction "VSSQ_44") (pintype "passive"))
      (node (ref "U1") (pin "63") (pinfunction "VSSQ_63") (pintype "passive"))
      (node (ref "U1") (pin "66") (pinfunction "GND_66") (pintype "passive"))
      (node (ref "U1") (pin "68") (pinfunction "GND_68") (pintype "passive"))
      (node (ref "U1") (pin "69") (pinfunction "GND_69") (pintype "passive"))
      (node (ref "U1") (pin "81") (pinfunction "VSS_81") (pintype "passive"))
      (node (ref "U1") (pin "98") (pinfunction "VSSQ_98") (pintype "passive"))
      (node (ref "U3") (pin "4") (pinfunction "GND_4") (pintype "passive"))
      (node (ref "USB1") (pin "4") (pinfunction "GND_4") (pintype "passive"))
      (node (ref "USB1") (pin "5") (pinfunction "GND_5") (pintype "passive"))
      (node (ref "USB1") (pin "6") (pinfunction "TBD_6") (pintype "passive"))
      (node (ref "USB1") (pin "7") (pinfunction "TBD_7") (pintype "passive"))
      (node (ref "USB1") (pin "8") (pinfunction "TBD_8") (pintype "passive"))
      (node (ref "USB1") (pin "9") (pinfunction "TBD_9") (pintype "passive"))
      (node (ref "Y2") (pin "2") (pinfunction "NC_2") (pintype "passive"))
      (node (ref "Y2") (pin "4") (pinfunction "NC_4") (pintype "passive"))
    )
    (net (code "79") (name "Net-(D2-Pad2)") (class "Default")
      (node (ref "D2") (pin "2") (pinfunction "2_2") (pintype "passive"))
      (node (ref "R2") (pin "1") (pinfunction "1_1") (pintype "passive"))
    )
    (net (code "80") (name "Net-(D3-Pad1)") (class "Default")
      (node (ref "D3") (pin "1") (pinfunction "1_1") (pintype "passive"))
      (node (ref "R1") (pin "2") (pinfunction "2_2") (pintype "passive"))
    )
    (net (code "81") (name "Net-(D4-Pad1)") (class "Default")
      (node (ref "D4") (pin "1") (pinfunction "1_1") (pintype "passive"))
      (node (ref "R10") (pin "2") (pinfunction "2_2") (pintype "passive"))
    )
    (net (code "82") (name "Net-(D9-Pad1)") (class "Default")
      (node (ref "D9") (pin "1") (pinfunction "1_1") (pintype "passive"))
      (node (ref "R51") (pin "2") (pinfunction "2_2") (pintype "passive"))
    )
    (net (code "83") (name "Net-(U1-OSC_IN)") (class "Default")
      (node (ref "C55") (pin "2") (pinfunction "2_2") (pintype "passive"))
      (node (ref "U1") (pin "9") (pinfunction "OSC_IN_9") (pintype "passive"))
      (node (ref "Y2") (pin "1") (pinfunction "X1_1") (pintype "passive"))
    )
    (net (code "84") (name "Net-(U1-OSC_OUT)") (class "Default")
      (node (ref "C56") (pin "2") (pinfunction "2_2") (pintype "passive"))
      (node (ref "U1") (pin "10") (pinfunction "OSC_OUT_10") (pintype "passive"))
      (node (ref "Y2") (pin "3") (pinfunction "X2_3") (pintype "passive"))
    )
    (net (code "85") (name "Net-(U1-PC0{slash}SPI4_CS{slash}IIC3_SDA)") (class "Default")
      (node (ref "P8") (pin "8") (pinfunction "8_8") (pintype "passive"))
      (node (ref "U1") (pin "113") (pinfunction "PC0/SPI4_CS/IIC3_SDA_113") (pintype "passive"))
    )
    (net (code "86") (name "Net-(U1-PC1{slash}SPI4_SCK{slash}IIC3_SCK)") (class "Default")
      (node (ref "P8") (pin "7") (pinfunction "7_7") (pintype "passive"))
      (node (ref "U1") (pin "114") (pinfunction "PC1/SPI4_SCK/IIC3_SCK_114") (pintype "passive"))
    )
    (net (code "87") (name "Net-(U1-PC2{slash}SPI4_MISO{slash}SDIO1_D2)") (class "Default")
      (node (ref "P8") (pin "6") (pinfunction "6_6") (pintype "passive"))
      (node (ref "U1") (pin "115") (pinfunction "PC2/SPI4_MISO/SDIO1_D2_115") (pintype "passive"))
    )
    (net (code "88") (name "Net-(U1-PC3{slash}SPI4_MOSI{slash}SDIO1_D3{slash}I2S_RX)") (class "Default")
      (node (ref "P8") (pin "5") (pinfunction "5_5") (pintype "passive"))
      (node (ref "U1") (pin "116") (pinfunction "PC3/SPI4_MOSI/SDIO1_D3/I2S_RX_116") (pintype "passive"))
    )
    (net (code "89") (name "Net-(U1-PC6{slash}SDIO1_D0{slash}I2S_BCLK)") (class "Default")
      (node (ref "P8") (pin "2") (pinfunction "2_2") (pintype "passive"))
      (node (ref "U1") (pin "119") (pinfunction "PC6/SDIO1_D0/I2S_BCLK_119") (pintype "passive"))
    )
    (net (code "90") (name "Net-(U1-PC7{slash}SDIO_D1{slash}I2S_MCLK)") (class "Default")
      (node (ref "P8") (pin "1") (pinfunction "1_1") (pintype "passive"))
      (node (ref "U1") (pin "120") (pinfunction "PC7/SDIO_D1/I2S_MCLK_120") (pintype "passive"))
    )
    (net (code "91") (name "Net-(U1-TIM7_CH1{slash}OSC32_IN{slash}PB14)") (class "Default")
      (node (ref "R1") (pin "1") (pinfunction "1_1") (pintype "passive"))
      (node (ref "U1") (pin "5") (pinfunction "TIM7_CH1/OSC32_IN/PB14_5") (pintype "passive"))
    )
    (net (code "92") (name "Net-(U1-TIM7_CH2{slash}OSC32_OUT{slash}PB15)") (class "Default")
      (node (ref "R10") (pin "1") (pinfunction "1_1") (pintype "passive"))
      (node (ref "U1") (pin "6") (pinfunction "TIM7_CH2/OSC32_OUT/PB15_6") (pintype "passive"))
    )
    (net (code "93") (name "Net-(U1-V-CAP)") (class "Default")
      (node (ref "C9") (pin "1") (pinfunction "1_1") (pintype "passive"))
      (node (ref "U1") (pin "123") (pinfunction "V-CAP_123") (pintype "passive"))
    )
    (net (code "94") (name "VCC") (class "Default")
      (node (ref "C15") (pin "1") (pinfunction "1_1") (pintype "passive"))
      (node (ref "C49") (pin "2") (pinfunction "2_2") (pintype "passive"))
      (node (ref "IC1") (pin "3") (pinfunction "IN_3") (pintype "passive"))
      (node (ref "P4") (pin "1") (pinfunction "1_1") (pintype "passive"))
      (node (ref "Switch_1") (pin "2") (pinfunction "CA_2") (pintype "passive"))
      (node (ref "Switch_1") (pin "3") (pinfunction "A2_3") (pintype "passive"))
      (node (ref "Switch_1") (pin "5") (pinfunction "CB_5") (pintype "passive"))
      (node (ref "Switch_1") (pin "6") (pinfunction "B2_6") (pintype "passive"))
    )
    (net (code "95") (name "VCC_IN") (class "Default")
      (node (ref "P5") (pin "3") (pinfunction "3_3") (pintype "passive"))
      (node (ref "P6") (pin "3") (pinfunction "3_3") (pintype "passive"))
      (node (ref "R14") (pin "1") (pinfunction "1_1") (pintype "passive"))
      (node (ref "R15") (pin "1") (pinfunction "1_1") (pintype "passive"))
      (node (ref "Switch_1") (pin "1") (pinfunction "A1_1") (pintype "passive"))
      (node (ref "Switch_1") (pin "4") (pinfunction "B1_4") (pintype "passive"))
      (node (ref "USB1") (pin "1") (pinfunction "VCC_1") (pintype "passive"))
    )
    (net (code "96") (name "unconnected-(P3-Pad9)") (class "Default")
      (node (ref "P3") (pin "9") (pinfunction "9_9") (pintype "passive+no_connect"))
    )
    (net (code "97") (name "unconnected-(SW2-Pad2)") (class "Default")
      (node (ref "SW2") (pin "2") (pinfunction "2_2") (pintype "passive"))
    )
    (net (code "98") (name "unconnected-(U1-NC-Pad3)") (class "Default")
      (node (ref "U1") (pin "3") (pinfunction "NC_3") (pintype "passive+no_connect"))
    )
    (net (code "99") (name "unconnected-(U1-NC-Pad12)") (class "Default")
      (node (ref "U1") (pin "12") (pinfunction "NC_12") (pintype "passive+no_connect"))
    )
    (net (code "100") (name "unconnected-(U1-NC-Pad13)") (class "Default")
      (node (ref "U1") (pin "13") (pinfunction "NC_13") (pintype "passive+no_connect"))
    )
    (net (code "101") (name "unconnected-(U1-NC-Pad14)") (class "Default")
      (node (ref "U1") (pin "14") (pinfunction "NC_14") (pintype "passive+no_connect"))
    )
    (net (code "102") (name "unconnected-(U1-NC-Pad15)") (class "Default")
      (node (ref "U1") (pin "15") (pinfunction "NC_15") (pintype "passive+no_connect"))
    )
    (net (code "103") (name "unconnected-(U1-NC-Pad21)") (class "Default")
      (node (ref "U1") (pin "21") (pinfunction "NC_21") (pintype "passive+no_connect"))
    )
    (net (code "104") (name "unconnected-(U1-NC-Pad22)") (class "Default")
      (node (ref "U1") (pin "22") (pinfunction "NC_22") (pintype "passive+no_connect"))
    )
  )
)
